# P06_LED_Config_Button.net
KiCad netlist of a schematic drawn in Altium Designer
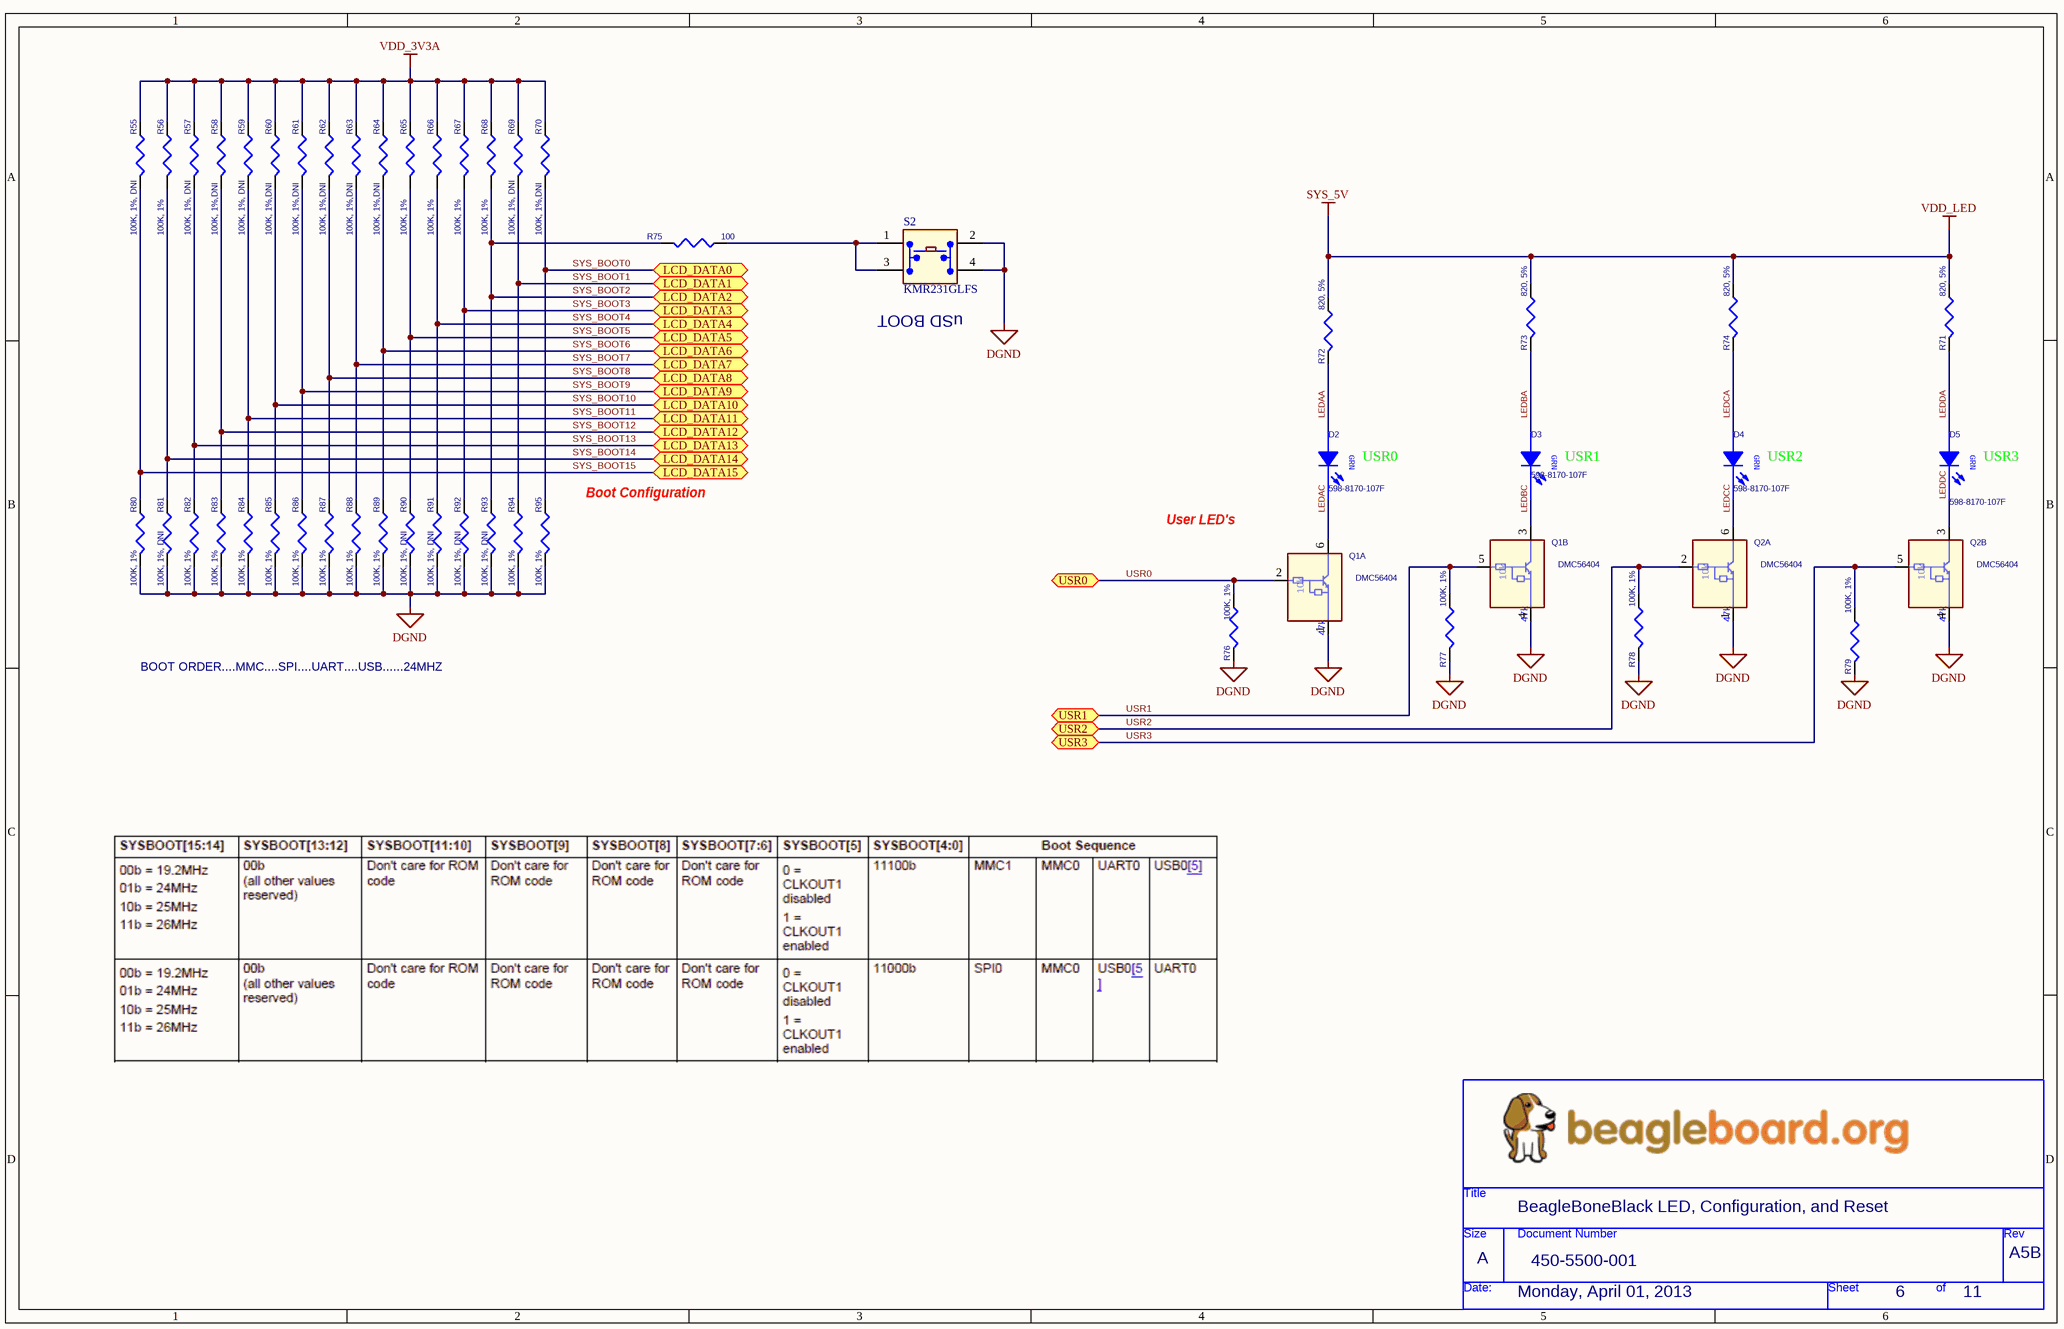
[diagram p0: P06_LED, Config, & Button.SchDoc]

(export (version "E")
  (design (tool "Eeschema 10.0.6"))
  (components
    (comp (ref "D2")
      (value "598-8170-107F")
      (footprint "LED_0603")
      (description "LED GREEN CLEAR 0805 SMD")
      (fields
        (field (name "MANUFACTURER") "Lite-On Inc")
        (field (name "MANUFACTURER PART NUMBER") "LTST-C170KGKT")
      )
      (libsource (lib "BEAGLEBONEBLACK_REV A5B") (part "LED_LTST-C150GKT"))
    )
    (comp (ref "D3")
      (value "598-8170-107F")
      (footprint "LED_0603")
      (description "LED GREEN CLEAR 0805 SMD")
      (fields
        (field (name "MANUFACTURER") "Lite-On Inc")
        (field (name "MANUFACTURER PART NUMBER") "LTST-C170KGKT")
      )
      (libsource (lib "BEAGLEBONEBLACK_REV A5B") (part "LED_LTST-C150GKT"))
    )
    (comp (ref "D4")
      (value "598-8170-107F")
      (footprint "LED_0603")
      (description "LED GREEN CLEAR 0805 SMD")
      (fields
        (field (name "MANUFACTURER") "Lite-On Inc")
        (field (name "MANUFACTURER PART NUMBER") "LTST-C170KGKT")
      )
      (libsource (lib "BEAGLEBONEBLACK_REV A5B") (part "LED_LTST-C150GKT"))
    )
    (comp (ref "D5")
      (value "598-8170-107F")
      (footprint "LED_0603")
      (description "LED GREEN CLEAR 0805 SMD")
      (fields
        (field (name "MANUFACTURER") "Lite-On Inc")
        (field (name "MANUFACTURER PART NUMBER") "LTST-C170KGKT")
      )
      (libsource (lib "BEAGLEBONEBLACK_REV A5B") (part "LED_LTST-C150GKT"))
    )
    (comp (ref "Q1")
      (value "DMC56404")
      (description "TRANS PREBIASED DUAL NPN SOT363")
      (fields
        (field (name "MANUFACTURER") "Toshiba")
        (field (name "MANUFACTURER PART NUMBER") "DDC114YU-7-F")
      )
      (libsource (lib "BEAGLEBONEBLACK_REV A5B") (part "RN1907"))
    )
    (comp (ref "Q2")
      (value "DMC56404")
      (description "TRANS PREBIASED DUAL NPN SOT363")
      (fields
        (field (name "MANUFACTURER") "Toshiba")
        (field (name "MANUFACTURER PART NUMBER") "DDC114YU-7-F")
      )
      (libsource (lib "BEAGLEBONEBLACK_REV A5B") (part "RN1907"))
    )
    (comp (ref "R55")
      (value "100K, 1%, DNI")
      (footprint "402")
      (description "RES 100K OHM 1/16W 1% 0402 SMD")
      (fields
        (field (name "MANUFACTURER") "Stackpole Electronics Inc")
        (field (name "MANUFACTURER PART NUMBER") "RMCF0402FT100K")
      )
      (libsource (lib "BEAGLEBONEBLACK_REV A5B") (part "RES_100K_1/16W_1%_0402"))
    )
    (comp (ref "R56")
      (value "100K, 1%")
      (footprint "402")
      (description "RES 100K OHM 1/16W 1% 0402 SMD")
      (fields
        (field (name "MANUFACTURER") "Stackpole Electronics Inc")
        (field (name "MANUFACTURER PART NUMBER") "RMCF0402FT100K")
      )
      (libsource (lib "BEAGLEBONEBLACK_REV A5B") (part "RES_100K_1/16W_1%_0402"))
    )
    (comp (ref "R57")
      (value "100K, 1%, DNI")
      (footprint "402")
      (description "RES 100K OHM 1/16W 1% 0402 SMD")
      (fields
        (field (name "MANUFACTURER") "Stackpole Electronics Inc")
        (field (name "MANUFACTURER PART NUMBER") "RMCF0402FT100K")
      )
      (libsource (lib "BEAGLEBONEBLACK_REV A5B") (part "RES_100K_1/16W_1%_0402"))
    )
    (comp (ref "R58")
      (value "100K, 1%,DNI")
      (footprint "402")
      (description "RES 100K OHM 1/16W 1% 0402 SMD")
      (fields
        (field (name "MANUFACTURER") "Stackpole Electronics Inc")
        (field (name "MANUFACTURER PART NUMBER") "RMCF0402FT100K")
      )
      (libsource (lib "BEAGLEBONEBLACK_REV A5B") (part "RES_100K_1/16W_1%_0402"))
    )
    (comp (ref "R59")
      (value "100K, 1%, DNI")
      (footprint "402")
      (description "RES 100K OHM 1/16W 1% 0402 SMD")
      (fields
        (field (name "MANUFACTURER") "Stackpole Electronics Inc")
        (field (name "MANUFACTURER PART NUMBER") "RMCF0402FT100K")
      )
      (libsource (lib "BEAGLEBONEBLACK_REV A5B") (part "RES_100K_1/16W_1%_0402"))
    )
    (comp (ref "R60")
      (value "100K, 1%,DNI")
      (footprint "402")
      (description "RES 100K OHM 1/16W 1% 0402 SMD")
      (fields
        (field (name "MANUFACTURER") "Stackpole Electronics Inc")
        (field (name "MANUFACTURER PART NUMBER") "RMCF0402FT100K")
      )
      (libsource (lib "BEAGLEBONEBLACK_REV A5B") (part "RES_100K_1/16W_1%_0402"))
    )
    (comp (ref "R61")
      (value "100K, 1%,DNI")
      (footprint "402")
      (description "RES 100K OHM 1/16W 1% 0402 SMD")
      (fields
        (field (name "MANUFACTURER") "Stackpole Electronics Inc")
        (field (name "MANUFACTURER PART NUMBER") "RMCF0402FT100K")
      )
      (libsource (lib "BEAGLEBONEBLACK_REV A5B") (part "RES_100K_1/16W_1%_0402"))
    )
    (comp (ref "R62")
      (value "100K, 1%,DNI")
      (footprint "402")
      (description "RES 100K OHM 1/16W 1% 0402 SMD")
      (fields
        (field (name "MANUFACTURER") "Stackpole Electronics Inc")
        (field (name "MANUFACTURER PART NUMBER") "RMCF0402FT100K")
      )
      (libsource (lib "BEAGLEBONEBLACK_REV A5B") (part "RES_100K_1/16W_1%_0402"))
    )
    (comp (ref "R63")
      (value "100K, 1%,DNI")
      (footprint "402")
      (description "RES 100K OHM 1/16W 1% 0402 SMD")
      (fields
        (field (name "MANUFACTURER") "Stackpole Electronics Inc")
        (field (name "MANUFACTURER PART NUMBER") "RMCF0402FT100K")
      )
      (libsource (lib "BEAGLEBONEBLACK_REV A5B") (part "RES_100K_1/16W_1%_0402"))
    )
    (comp (ref "R64")
      (value "100K, 1%,DNI")
      (footprint "402")
      (description "RES 100K OHM 1/16W 1% 0402 SMD")
      (fields
        (field (name "MANUFACTURER") "Stackpole Electronics Inc")
        (field (name "MANUFACTURER PART NUMBER") "RMCF0402FT100K")
      )
      (libsource (lib "BEAGLEBONEBLACK_REV A5B") (part "RES_100K_1/16W_1%_0402"))
    )
    (comp (ref "R65")
      (value "100K, 1%")
      (footprint "402")
      (description "RES 100K OHM 1/16W 1% 0402 SMD")
      (fields
        (field (name "MANUFACTURER") "Stackpole Electronics Inc")
        (field (name "MANUFACTURER PART NUMBER") "RMCF0402FT100K")
      )
      (libsource (lib "BEAGLEBONEBLACK_REV A5B") (part "RES_100K_1/16W_1%_0402"))
    )
    (comp (ref "R66")
      (value "100K, 1%")
      (footprint "402")
      (description "RES 100K OHM 1/16W 1% 0402 SMD")
      (fields
        (field (name "MANUFACTURER") "Stackpole Electronics Inc")
        (field (name "MANUFACTURER PART NUMBER") "RMCF0402FT100K")
      )
      (libsource (lib "BEAGLEBONEBLACK_REV A5B") (part "RES_100K_1/16W_1%_0402"))
    )
    (comp (ref "R67")
      (value "100K, 1%")
      (footprint "402")
      (description "RES 100K OHM 1/16W 1% 0402 SMD")
      (fields
        (field (name "MANUFACTURER") "Stackpole Electronics Inc")
        (field (name "MANUFACTURER PART NUMBER") "RMCF0402FT100K")
      )
      (libsource (lib "BEAGLEBONEBLACK_REV A5B") (part "RES_100K_1/16W_1%_0402"))
    )
    (comp (ref "R68")
      (value "100K, 1%")
      (footprint "402")
      (description "RES 100K OHM 1/16W 1% 0402 SMD")
      (fields
        (field (name "MANUFACTURER") "Stackpole Electronics Inc")
        (field (name "MANUFACTURER PART NUMBER") "RMCF0402FT100K")
      )
      (libsource (lib "BEAGLEBONEBLACK_REV A5B") (part "RES_100K_1/16W_1%_0402"))
    )
    (comp (ref "R69")
      (value "100K, 1%, DNI")
      (footprint "402")
      (description "RES 100K OHM 1/16W 1% 0402 SMD")
      (fields
        (field (name "MANUFACTURER") "Stackpole Electronics Inc")
        (field (name "MANUFACTURER PART NUMBER") "RMCF0402FT100K")
      )
      (libsource (lib "BEAGLEBONEBLACK_REV A5B") (part "RES_100K_1/16W_1%_0402"))
    )
    (comp (ref "R70")
      (value "100K, 1%,DNI")
      (footprint "402")
      (description "RES 100K OHM 1/16W 1% 0402 SMD")
      (fields
        (field (name "MANUFACTURER") "Stackpole Electronics Inc")
        (field (name "MANUFACTURER PART NUMBER") "RMCF0402FT100K")
      )
      (libsource (lib "BEAGLEBONEBLACK_REV A5B") (part "RES_100K_1/16W_1%_0402"))
    )
    (comp (ref "R71")
      (value "820, 5%")
      (footprint "402")
      (description "RES 820 OHM 1/10W 5% 0402 SMD")
      (fields
        (field (name "MANUFACTURER") "Yageo")
        (field (name "MANUFACTURER PART NUMBER") "RC0402JR-07820RL")
      )
      (libsource (lib "BEAGLEBONEBLACK_REV A5B") (part "RES_470_1/10W_5%_0402"))
    )
    (comp (ref "R72")
      (value "820, 5%")
      (footprint "402")
      (description "RES 820 OHM 1/10W 5% 0402 SMD")
      (fields
        (field (name "MANUFACTURER") "Yageo")
        (field (name "MANUFACTURER PART NUMBER") "RC0402JR-07820RL")
      )
      (libsource (lib "BEAGLEBONEBLACK_REV A5B") (part "RES_470_1/10W_5%_0402"))
    )
    (comp (ref "R73")
      (value "820, 5%")
      (footprint "402")
      (description "RES 820 OHM 1/10W 5% 0402 SMD")
      (fields
        (field (name "MANUFACTURER") "Yageo")
        (field (name "MANUFACTURER PART NUMBER") "RC0402JR-07820RL")
      )
      (libsource (lib "BEAGLEBONEBLACK_REV A5B") (part "RES_470_1/10W_5%_0402"))
    )
    (comp (ref "R74")
      (value "820, 5%")
      (footprint "402")
      (description "RES 820 OHM 1/10W 5% 0402 SMD")
      (fields
        (field (name "MANUFACTURER") "Yageo")
        (field (name "MANUFACTURER PART NUMBER") "RC0402JR-07820RL")
      )
      (libsource (lib "BEAGLEBONEBLACK_REV A5B") (part "RES_470_1/10W_5%_0402"))
    )
    (comp (ref "R75")
      (value "100")
      (footprint "402")
      (description "RES 100 OHM 1/10W 5% 0402 SMD")
      (fields
        (field (name "MANUFACTURER") "Panasonic Electronic Components")
        (field (name "MANUFACTURER PART NUMBER") "ERJ-2RKF1000X")
      )
      (libsource (lib "BEAGLEBONEBLACK_REV A5B") (part "RES SMD"))
    )
    (comp (ref "R76")
      (value "100K, 1%")
      (footprint "402")
      (description "RES 100K OHM 1/16W 1% 0402 SMD")
      (fields
        (field (name "MANUFACTURER") "Stackpole Electronics Inc")
        (field (name "MANUFACTURER PART NUMBER") "RMCF0402FT100K")
      )
      (libsource (lib "BEAGLEBONEBLACK_REV A5B") (part "RES_100K_1/16W_1%_0402"))
    )
    (comp (ref "R77")
      (value "100K, 1%")
      (footprint "402")
      (description "RES 100K OHM 1/16W 1% 0402 SMD")
      (fields
        (field (name "MANUFACTURER") "Stackpole Electronics Inc")
        (field (name "MANUFACTURER PART NUMBER") "RMCF0402FT100K")
      )
      (libsource (lib "BEAGLEBONEBLACK_REV A5B") (part "RES_100K_1/16W_1%_0402"))
    )
    (comp (ref "R78")
      (value "100K, 1%")
      (footprint "402")
      (description "RES 100K OHM 1/16W 1% 0402 SMD")
      (fields
        (field (name "MANUFACTURER") "Stackpole Electronics Inc")
        (field (name "MANUFACTURER PART NUMBER") "RMCF0402FT100K")
      )
      (libsource (lib "BEAGLEBONEBLACK_REV A5B") (part "RES_100K_1/16W_1%_0402"))
    )
    (comp (ref "R79")
      (value "100K, 1%")
      (footprint "402")
      (description "RES 100K OHM 1/16W 1% 0402 SMD")
      (fields
        (field (name "MANUFACTURER") "Stackpole Electronics Inc")
        (field (name "MANUFACTURER PART NUMBER") "RMCF0402FT100K")
      )
      (libsource (lib "BEAGLEBONEBLACK_REV A5B") (part "RES_100K_1/16W_1%_0402"))
    )
    (comp (ref "R80")
      (value "100K, 1%")
      (footprint "402")
      (description "RES 100K OHM 1/16W 1% 0402 SMD")
      (fields
        (field (name "MANUFACTURER") "Stackpole Electronics Inc")
        (field (name "MANUFACTURER PART NUMBER") "RMCF0402FT100K")
      )
      (libsource (lib "BEAGLEBONEBLACK_REV A5B") (part "RES_100K_1/16W_1%_0402"))
    )
    (comp (ref "R81")
      (value "100K, 1%, DNI")
      (footprint "402")
      (description "RES 100K OHM 1/16W 1% 0402 SMD")
      (fields
        (field (name "MANUFACTURER") "Stackpole Electronics Inc")
        (field (name "MANUFACTURER PART NUMBER") "RMCF0402FT100K")
      )
      (libsource (lib "BEAGLEBONEBLACK_REV A5B") (part "RES_100K_1/16W_1%_0402"))
    )
    (comp (ref "R82")
      (value "100K, 1%")
      (footprint "402")
      (description "RES 100K OHM 1/16W 1% 0402 SMD")
      (fields
        (field (name "MANUFACTURER") "Stackpole Electronics Inc")
        (field (name "MANUFACTURER PART NUMBER") "RMCF0402FT100K")
      )
      (libsource (lib "BEAGLEBONEBLACK_REV A5B") (part "RES_100K_1/16W_1%_0402"))
    )
    (comp (ref "R83")
      (value "100K, 1%")
      (footprint "402")
      (description "RES 100K OHM 1/16W 1% 0402 SMD")
      (fields
        (field (name "MANUFACTURER") "Stackpole Electronics Inc")
        (field (name "MANUFACTURER PART NUMBER") "RMCF0402FT100K")
      )
      (libsource (lib "BEAGLEBONEBLACK_REV A5B") (part "RES_100K_1/16W_1%_0402"))
    )
    (comp (ref "R84")
      (value "100K, 1%")
      (footprint "402")
      (description "RES 100K OHM 1/16W 1% 0402 SMD")
      (fields
        (field (name "MANUFACTURER") "Stackpole Electronics Inc")
        (field (name "MANUFACTURER PART NUMBER") "RMCF0402FT100K")
      )
      (libsource (lib "BEAGLEBONEBLACK_REV A5B") (part "RES_100K_1/16W_1%_0402"))
    )
    (comp (ref "R85")
      (value "100K, 1%")
      (footprint "402")
      (description "RES 100K OHM 1/16W 1% 0402 SMD")
      (fields
        (field (name "MANUFACTURER") "Stackpole Electronics Inc")
        (field (name "MANUFACTURER PART NUMBER") "RMCF0402FT100K")
      )
      (libsource (lib "BEAGLEBONEBLACK_REV A5B") (part "RES_100K_1/16W_1%_0402"))
    )
    (comp (ref "R86")
      (value "100K, 1%")
      (footprint "402")
      (description "RES 100K OHM 1/16W 1% 0402 SMD")
      (fields
        (field (name "MANUFACTURER") "Stackpole Electronics Inc")
        (field (name "MANUFACTURER PART NUMBER") "RMCF0402FT100K")
      )
      (libsource (lib "BEAGLEBONEBLACK_REV A5B") (part "RES_100K_1/16W_1%_0402"))
    )
    (comp (ref "R87")
      (value "100K, 1%")
      (footprint "402")
      (description "RES 100K OHM 1/16W 1% 0402 SMD")
      (fields
        (field (name "MANUFACTURER") "Stackpole Electronics Inc")
        (field (name "MANUFACTURER PART NUMBER") "RMCF0402FT100K")
      )
      (libsource (lib "BEAGLEBONEBLACK_REV A5B") (part "RES_100K_1/16W_1%_0402"))
    )
    (comp (ref "R88")
      (value "100K, 1%")
      (footprint "402")
      (description "RES 100K OHM 1/16W 1% 0402 SMD")
      (fields
        (field (name "MANUFACTURER") "Stackpole Electronics Inc")
        (field (name "MANUFACTURER PART NUMBER") "RMCF0402FT100K")
      )
      (libsource (lib "BEAGLEBONEBLACK_REV A5B") (part "RES_100K_1/16W_1%_0402"))
    )
    (comp (ref "R89")
      (value "100K, 1%")
      (footprint "402")
      (description "RES 100K OHM 1/16W 1% 0402 SMD")
      (fields
        (field (name "MANUFACTURER") "Stackpole Electronics Inc")
        (field (name "MANUFACTURER PART NUMBER") "RMCF0402FT100K")
      )
      (libsource (lib "BEAGLEBONEBLACK_REV A5B") (part "RES_100K_1/16W_1%_0402"))
    )
    (comp (ref "R90")
      (value "100K, 1%, DNI")
      (footprint "402")
      (description "RES 100K OHM 1/16W 1% 0402 SMD")
      (fields
        (field (name "MANUFACTURER") "Stackpole Electronics Inc")
        (field (name "MANUFACTURER PART NUMBER") "RMCF0402FT100K")
      )
      (libsource (lib "BEAGLEBONEBLACK_REV A5B") (part "RES_100K_1/16W_1%_0402"))
    )
    (comp (ref "R91")
      (value "100K, 1%, DNI")
      (footprint "402")
      (description "RES 100K OHM 1/16W 1% 0402 SMD")
      (fields
        (field (name "MANUFACTURER") "Stackpole Electronics Inc")
        (field (name "MANUFACTURER PART NUMBER") "RMCF0402FT100K")
      )
      (libsource (lib "BEAGLEBONEBLACK_REV A5B") (part "RES_100K_1/16W_1%_0402"))
    )
    (comp (ref "R92")
      (value "100K, 1%, DNI")
      (footprint "402")
      (description "RES 100K OHM 1/16W 1% 0402 SMD")
      (fields
        (field (name "MANUFACTURER") "Stackpole Electronics Inc")
        (field (name "MANUFACTURER PART NUMBER") "RMCF0402FT100K")
      )
      (libsource (lib "BEAGLEBONEBLACK_REV A5B") (part "RES_100K_1/16W_1%_0402"))
    )
    (comp (ref "R93")
      (value "100K, 1%, DNI")
      (footprint "402")
      (description "RES 100K OHM 1/16W 1% 0402 SMD")
      (fields
        (field (name "MANUFACTURER") "Stackpole Electronics Inc")
        (field (name "MANUFACTURER PART NUMBER") "RMCF0402FT100K")
      )
      (libsource (lib "BEAGLEBONEBLACK_REV A5B") (part "RES_100K_1/16W_1%_0402"))
    )
    (comp (ref "R94")
      (value "100K, 1%")
      (footprint "402")
      (description "RES 100K OHM 1/16W 1% 0402 SMD")
      (fields
        (field (name "MANUFACTURER") "Stackpole Electronics Inc")
        (field (name "MANUFACTURER PART NUMBER") "RMCF0402FT100K")
      )
      (libsource (lib "BEAGLEBONEBLACK_REV A5B") (part "RES_100K_1/16W_1%_0402"))
    )
    (comp (ref "R95")
      (value "100K, 1%")
      (footprint "402")
      (description "RES 100K OHM 1/16W 1% 0402 SMD")
      (fields
        (field (name "MANUFACTURER") "Stackpole Electronics Inc")
        (field (name "MANUFACTURER PART NUMBER") "RMCF0402FT100K")
      )
      (libsource (lib "BEAGLEBONEBLACK_REV A5B") (part "RES_100K_1/16W_1%_0402"))
    )
    (comp (ref "S2")
      (value "KMR231GLFS")
      (footprint "SW4SMD_63X161LS")
      (description "Microminiature Tact Switch for SMT")
      (fields (field (name "MANUFACTURER") "C&K Components"))
      (libsource (lib "BEAGLEBONEBLACK_REV A5B") (part "KMR2"))
    )
  )
  (nets
    (net (code "1") (name "/LEDAA") (class "Default")
      (node (ref "D2") (pin "2") (pinfunction "A_2") (pintype "passive"))
      (node (ref "R72") (pin "2") (pinfunction "2_2") (pintype "passive"))
    )
    (net (code "2") (name "/LEDAC") (class "Default")
      (node (ref "D2") (pin "1") (pinfunction "C_1") (pintype "passive"))
      (node (ref "Q1") (pin "6") (pinfunction "3_6") (pintype "passive"))
    )
    (net (code "3") (name "/LEDBA") (class "Default")
      (node (ref "D3") (pin "2") (pinfunction "A_2") (pintype "passive"))
      (node (ref "R73") (pin "2") (pinfunction "2_2") (pintype "passive"))
    )
    (net (code "4") (name "/LEDBC") (class "Default")
      (node (ref "D3") (pin "1") (pinfunction "C_1") (pintype "passive"))
      (node (ref "Q1") (pin "3") (pinfunction "3_3") (pintype "passive"))
    )
    (net (code "5") (name "/LEDCA") (class "Default")
      (node (ref "D4") (pin "2") (pinfunction "A_2") (pintype "passive"))
      (node (ref "R74") (pin "2") (pinfunction "2_2") (pintype "passive"))
    )
    (net (code "6") (name "/LEDCC") (class "Default")
      (node (ref "D4") (pin "1") (pinfunction "C_1") (pintype "passive"))
      (node (ref "Q2") (pin "6") (pinfunction "3_6") (pintype "passive"))
    )
    (net (code "7") (name "/LEDDA") (class "Default")
      (node (ref "D5") (pin "2") (pinfunction "A_2") (pintype "passive"))
      (node (ref "R71") (pin "2") (pinfunction "2_2") (pintype "passive"))
    )
    (net (code "8") (name "/LEDDC") (class "Default")
      (node (ref "D5") (pin "1") (pinfunction "C_1") (pintype "passive"))
      (node (ref "Q2") (pin "3") (pinfunction "3_3") (pintype "passive"))
    )
    (net (code "9") (name "/SYS_BOOT0") (class "Default")
      (node (ref "R70") (pin "2") (pinfunction "2_2") (pintype "passive"))
      (node (ref "R95") (pin "1") (pinfunction "1_1") (pintype "passive"))
    )
    (net (code "10") (name "/SYS_BOOT1") (class "Default")
      (node (ref "R69") (pin "2") (pinfunction "2_2") (pintype "passive"))
      (node (ref "R94") (pin "1") (pinfunction "1_1") (pintype "passive"))
    )
    (net (code "11") (name "/SYS_BOOT2") (class "Default")
      (node (ref "R68") (pin "2") (pinfunction "2_2") (pintype "passive"))
      (node (ref "R75") (pin "1") (pinfunction "P1_1") (pintype "passive"))
      (node (ref "R93") (pin "1") (pinfunction "1_1") (pintype "passive"))
    )
    (net (code "12") (name "/SYS_BOOT3") (class "Default")
      (node (ref "R67") (pin "2") (pinfunction "2_2") (pintype "passive"))
      (node (ref "R92") (pin "1") (pinfunction "1_1") (pintype "passive"))
    )
    (net (code "13") (name "/SYS_BOOT4") (class "Default")
      (node (ref "R66") (pin "2") (pinfunction "2_2") (pintype "passive"))
      (node (ref "R91") (pin "1") (pinfunction "1_1") (pintype "passive"))
    )
    (net (code "14") (name "/SYS_BOOT5") (class "Default")
      (node (ref "R65") (pin "2") (pinfunction "2_2") (pintype "passive"))
      (node (ref "R90") (pin "1") (pinfunction "1_1") (pintype "passive"))
    )
    (net (code "15") (name "/SYS_BOOT6") (class "Default")
      (node (ref "R64") (pin "2") (pinfunction "2_2") (pintype "passive"))
      (node (ref "R89") (pin "1") (pinfunction "1_1") (pintype "passive"))
    )
    (net (code "16") (name "/SYS_BOOT7") (class "Default")
      (node (ref "R63") (pin "2") (pinfunction "2_2") (pintype "passive"))
      (node (ref "R88") (pin "1") (pinfunction "1_1") (pintype "passive"))
    )
    (net (code "17") (name "/SYS_BOOT8") (class "Default")
      (node (ref "R62") (pin "2") (pinfunction "2_2") (pintype "passive"))
      (node (ref "R87") (pin "1") (pinfunction "1_1") (pintype "passive"))
    )
    (net (code "18") (name "/SYS_BOOT9") (class "Default")
      (node (ref "R61") (pin "2") (pinfunction "2_2") (pintype "passive"))
      (node (ref "R86") (pin "1") (pinfunction "1_1") (pintype "passive"))
    )
    (net (code "19") (name "/SYS_BOOT10") (class "Default")
      (node (ref "R60") (pin "2") (pinfunction "2_2") (pintype "passive"))
      (node (ref "R85") (pin "1") (pinfunction "1_1") (pintype "passive"))
    )
    (net (code "20") (name "/SYS_BOOT11") (class "Default")
      (node (ref "R59") (pin "2") (pinfunction "2_2") (pintype "passive"))
      (node (ref "R84") (pin "1") (pinfunction "1_1") (pintype "passive"))
    )
    (net (code "21") (name "/SYS_BOOT12") (class "Default")
      (node (ref "R58") (pin "2") (pinfunction "2_2") (pintype "passive"))
      (node (ref "R83") (pin "1") (pinfunction "1_1") (pintype "passive"))
    )
    (net (code "22") (name "/SYS_BOOT13") (class "Default")
      (node (ref "R57") (pin "2") (pinfunction "2_2") (pintype "passive"))
      (node (ref "R82") (pin "1") (pinfunction "1_1") (pintype "passive"))
    )
    (net (code "23") (name "/SYS_BOOT14") (class "Default")
      (node (ref "R56") (pin "2") (pinfunction "2_2") (pintype "passive"))
      (node (ref "R81") (pin "1") (pinfunction "1_1") (pintype "passive"))
    )
    (net (code "24") (name "/SYS_BOOT15") (class "Default")
      (node (ref "R55") (pin "2") (pinfunction "2_2") (pintype "passive"))
      (node (ref "R80") (pin "1") (pinfunction "1_1") (pintype "passive"))
    )
    (net (code "25") (name "/USR0") (class "Default")
      (node (ref "Q1") (pin "2") (pinfunction "5_2") (pintype "passive"))
      (node (ref "R76") (pin "1") (pinfunction "1_1") (pintype "passive"))
    )
    (net (code "26") (name "/USR1") (class "Default")
      (node (ref "Q1") (pin "5") (pinfunction "5_5") (pintype "passive"))
      (node (ref "R77") (pin "1") (pinfunction "1_1") (pintype "passive"))
    )
    (net (code "27") (name "/USR2") (class "Default")
      (node (ref "Q2") (pin "2") (pinfunction "5_2") (pintype "passive"))
      (node (ref "R78") (pin "1") (pinfunction "1_1") (pintype "passive"))
    )
    (net (code "28") (name "/USR3") (class "Default")
      (node (ref "Q2") (pin "5") (pinfunction "5_5") (pintype "passive"))
      (node (ref "R79") (pin "1") (pinfunction "1_1") (pintype "passive"))
    )
    (net (code "29") (name "DGND") (class "Default")
      (node (ref "Q1") (pin "1") (pinfunction "4_1") (pintype "passive"))
      (node (ref "Q1") (pin "4") (pinfunction "4_4") (pintype "passive"))
      (node (ref "Q2") (pin "1") (pinfunction "4_1") (pintype "passive"))
      (node (ref "Q2") (pin "4") (pinfunction "4_4") (pintype "passive"))
      (node (ref "R76") (pin "2") (pinfunction "2_2") (pintype "passive"))
      (node (ref "R77") (pin "2") (pinfunction "2_2") (pintype "passive"))
      (node (ref "R78") (pin "2") (pinfunction "2_2") (pintype "passive"))
      (node (ref "R79") (pin "2") (pinfunction "2_2") (pintype "passive"))
      (node (ref "R80") (pin "2") (pinfunction "2_2") (pintype "passive"))
      (node (ref "R81") (pin "2") (pinfunction "2_2") (pintype "passive"))
      (node (ref "R82") (pin "2") (pinfunction "2_2") (pintype "passive"))
      (node (ref "R83") (pin "2") (pinfunction "2_2") (pintype "passive"))
      (node (ref "R84") (pin "2") (pinfunction "2_2") (pintype "passive"))
      (node (ref "R85") (pin "2") (pinfunction "2_2") (pintype "passive"))
      (node (ref "R86") (pin "2") (pinfunction "2_2") (pintype "passive"))
      (node (ref "R87") (pin "2") (pinfunction "2_2") (pintype "passive"))
      (node (ref "R88") (pin "2") (pinfunction "2_2") (pintype "passive"))
      (node (ref "R89") (pin "2") (pinfunction "2_2") (pintype "passive"))
      (node (ref "R90") (pin "2") (pinfunction "2_2") (pintype "passive"))
      (node (ref "R91") (pin "2") (pinfunction "2_2") (pintype "passive"))
      (node (ref "R92") (pin "2") (pinfunction "2_2") (pintype "passive"))
      (node (ref "R93") (pin "2") (pinfunction "2_2") (pintype "passive"))
      (node (ref "R94") (pin "2") (pinfunction "2_2") (pintype "passive"))
      (node (ref "R95") (pin "2") (pinfunction "2_2") (pintype "passive"))
      (node (ref "S2") (pin "2") (pinfunction "A2_2") (pintype "passive"))
      (node (ref "S2") (pin "4") (pinfunction "4_4") (pintype "power_in"))
    )
    (net (code "30") (name "Net-(R75-P2)") (class "Default")
      (node (ref "R75") (pin "2") (pinfunction "P2_2") (pintype "passive"))
      (node (ref "S2") (pin "1") (pinfunction "A1_1") (pintype "passive"))
      (node (ref "S2") (pin "3") (pinfunction "A3_3") (pintype "passive"))
    )
    (net (code "31") (name "SYS_5V") (class "Default")
      (node (ref "R71") (pin "1") (pinfunction "1_1") (pintype "passive"))
      (node (ref "R72") (pin "1") (pinfunction "1_1") (pintype "passive"))
      (node (ref "R73") (pin "1") (pinfunction "1_1") (pintype "passive"))
      (node (ref "R74") (pin "1") (pinfunction "1_1") (pintype "passive"))
    )
    (net (code "32") (name "VDD_3V3A") (class "Default")
      (node (ref "R55") (pin "1") (pinfunction "1_1") (pintype "passive"))
      (node (ref "R56") (pin "1") (pinfunction "1_1") (pintype "passive"))
      (node (ref "R57") (pin "1") (pinfunction "1_1") (pintype "passive"))
      (node (ref "R58") (pin "1") (pinfunction "1_1") (pintype "passive"))
      (node (ref "R59") (pin "1") (pinfunction "1_1") (pintype "passive"))
      (node (ref "R60") (pin "1") (pinfunction "1_1") (pintype "passive"))
      (node (ref "R61") (pin "1") (pinfunction "1_1") (pintype "passive"))
      (node (ref "R62") (pin "1") (pinfunction "1_1") (pintype "passive"))
      (node (ref "R63") (pin "1") (pinfunction "1_1") (pintype "passive"))
      (node (ref "R64") (pin "1") (pinfunction "1_1") (pintype "passive"))
      (node (ref "R65") (pin "1") (pinfunction "1_1") (pintype "passive"))
      (node (ref "R66") (pin "1") (pinfunction "1_1") (pintype "passive"))
      (node (ref "R67") (pin "1") (pinfunction "1_1") (pintype "passive"))
      (node (ref "R68") (pin "1") (pinfunction "1_1") (pintype "passive"))
      (node (ref "R69") (pin "1") (pinfunction "1_1") (pintype "passive"))
      (node (ref "R70") (pin "1") (pinfunction "1_1") (pintype "passive"))
    )
  )
)
